# Digital_In.net
KiCad netlist of a schematic drawn in Altium Designer
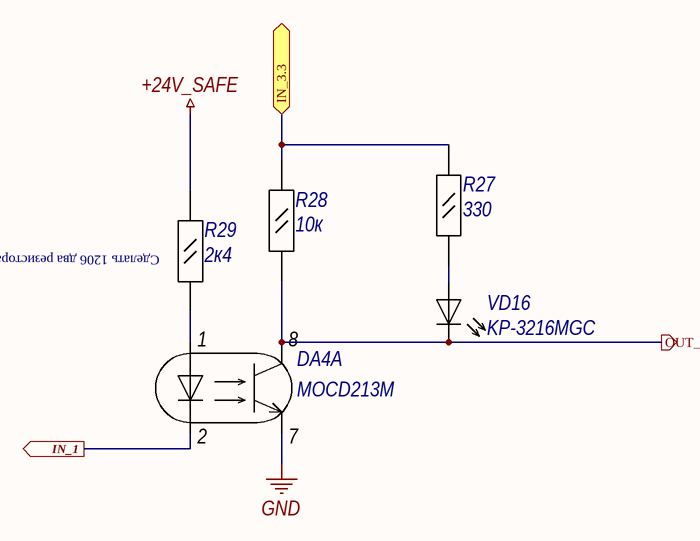
[diagram p0: Digital_In.SchDoc]

(export (version "E")
  (design (tool "Eeschema 10.0.6"))
  (components
    (comp (ref "DA4")
      (value "MOCD213M")
      (footprint "SO-8")
      (description "Оптопара 2 канала")
      (fields (field (name "MANUFACTURER") "Fairchild"))
      (libsource (lib "Micro_Analog") (part "MOCD213M"))
    )
    (comp (ref "R27")
      (value "330")
      (footprint "0805")
      (description "Резистор общего назначения 5%")
      (fields (field (name "MANUFACTURER") "YAGEO"))
      (libsource (lib "DX_test_lib2") (part "RC0805JR"))
    )
    (comp (ref "R28")
      (value "10к")
      (footprint "0805")
      (description "Резистор общего назначения 5%")
      (fields (field (name "MANUFACTURER") "YAGEO"))
      (libsource (lib "DX_test_lib2") (part "RC0805JR"))
    )
    (comp (ref "R29")
      (value "2к4")
      (footprint "0805")
      (description "Резистор общего назначения 5%")
      (fields (field (name "MANUFACTURER") "YAGEO"))
      (libsource (lib "DX_test_lib2") (part "RC0805JR"))
    )
    (comp (ref "VD16")
      (value "KP-3216MGC")
      (footprint "LED3216")
      (description "Светодиод")
      (fields (field (name "MANUFACTURER") "Kingbright"))
      (libsource (lib "DX_test_lib2") (part "KP-3216"))
    )
  )
  (nets
    (net (code "1") (name "+24V_SAFE") (class "Default")
      (node (ref "R29") (pin "2") (pinfunction "2_2") (pintype "passive"))
    )
    (net (code "2") (name "/IN_1") (class "Default")
      (node (ref "DA4") (pin "2") (pinfunction "CATHODE1_2") (pintype "passive"))
    )
    (net (code "3") (name "/IN_3.3") (class "Default")
      (node (ref "R27") (pin "1") (pinfunction "1_1") (pintype "passive"))
      (node (ref "R28") (pin "2") (pinfunction "2_2") (pintype "passive"))
    )
    (net (code "4") (name "/OUT_1") (class "Default")
      (node (ref "DA4") (pin "8") (pinfunction "C1_8") (pintype "passive"))
      (node (ref "R28") (pin "1") (pinfunction "1_1") (pintype "passive"))
      (node (ref "VD16") (pin "2") (pinfunction "K_2") (pintype "passive"))
    )
    (net (code "5") (name "GND") (class "Default")
      (node (ref "DA4") (pin "7") (pinfunction "E1_7") (pintype "passive"))
    )
    (net (code "6") (name "Net-(DA4A-ANODE1)") (class "Default")
      (node (ref "DA4") (pin "1") (pinfunction "ANODE1_1") (pintype "passive"))
      (node (ref "R29") (pin "1") (pinfunction "1_1") (pintype "passive"))
    )
    (net (code "7") (name "Net-(VD16-A)") (class "Default")
      (node (ref "R27") (pin "2") (pinfunction "2_2") (pintype "passive"))
      (node (ref "VD16") (pin "1") (pinfunction "A_1") (pintype "passive"))
    )
  )
)
